# OTHER.net
KiCad netlist of a schematic drawn in Altium Designer
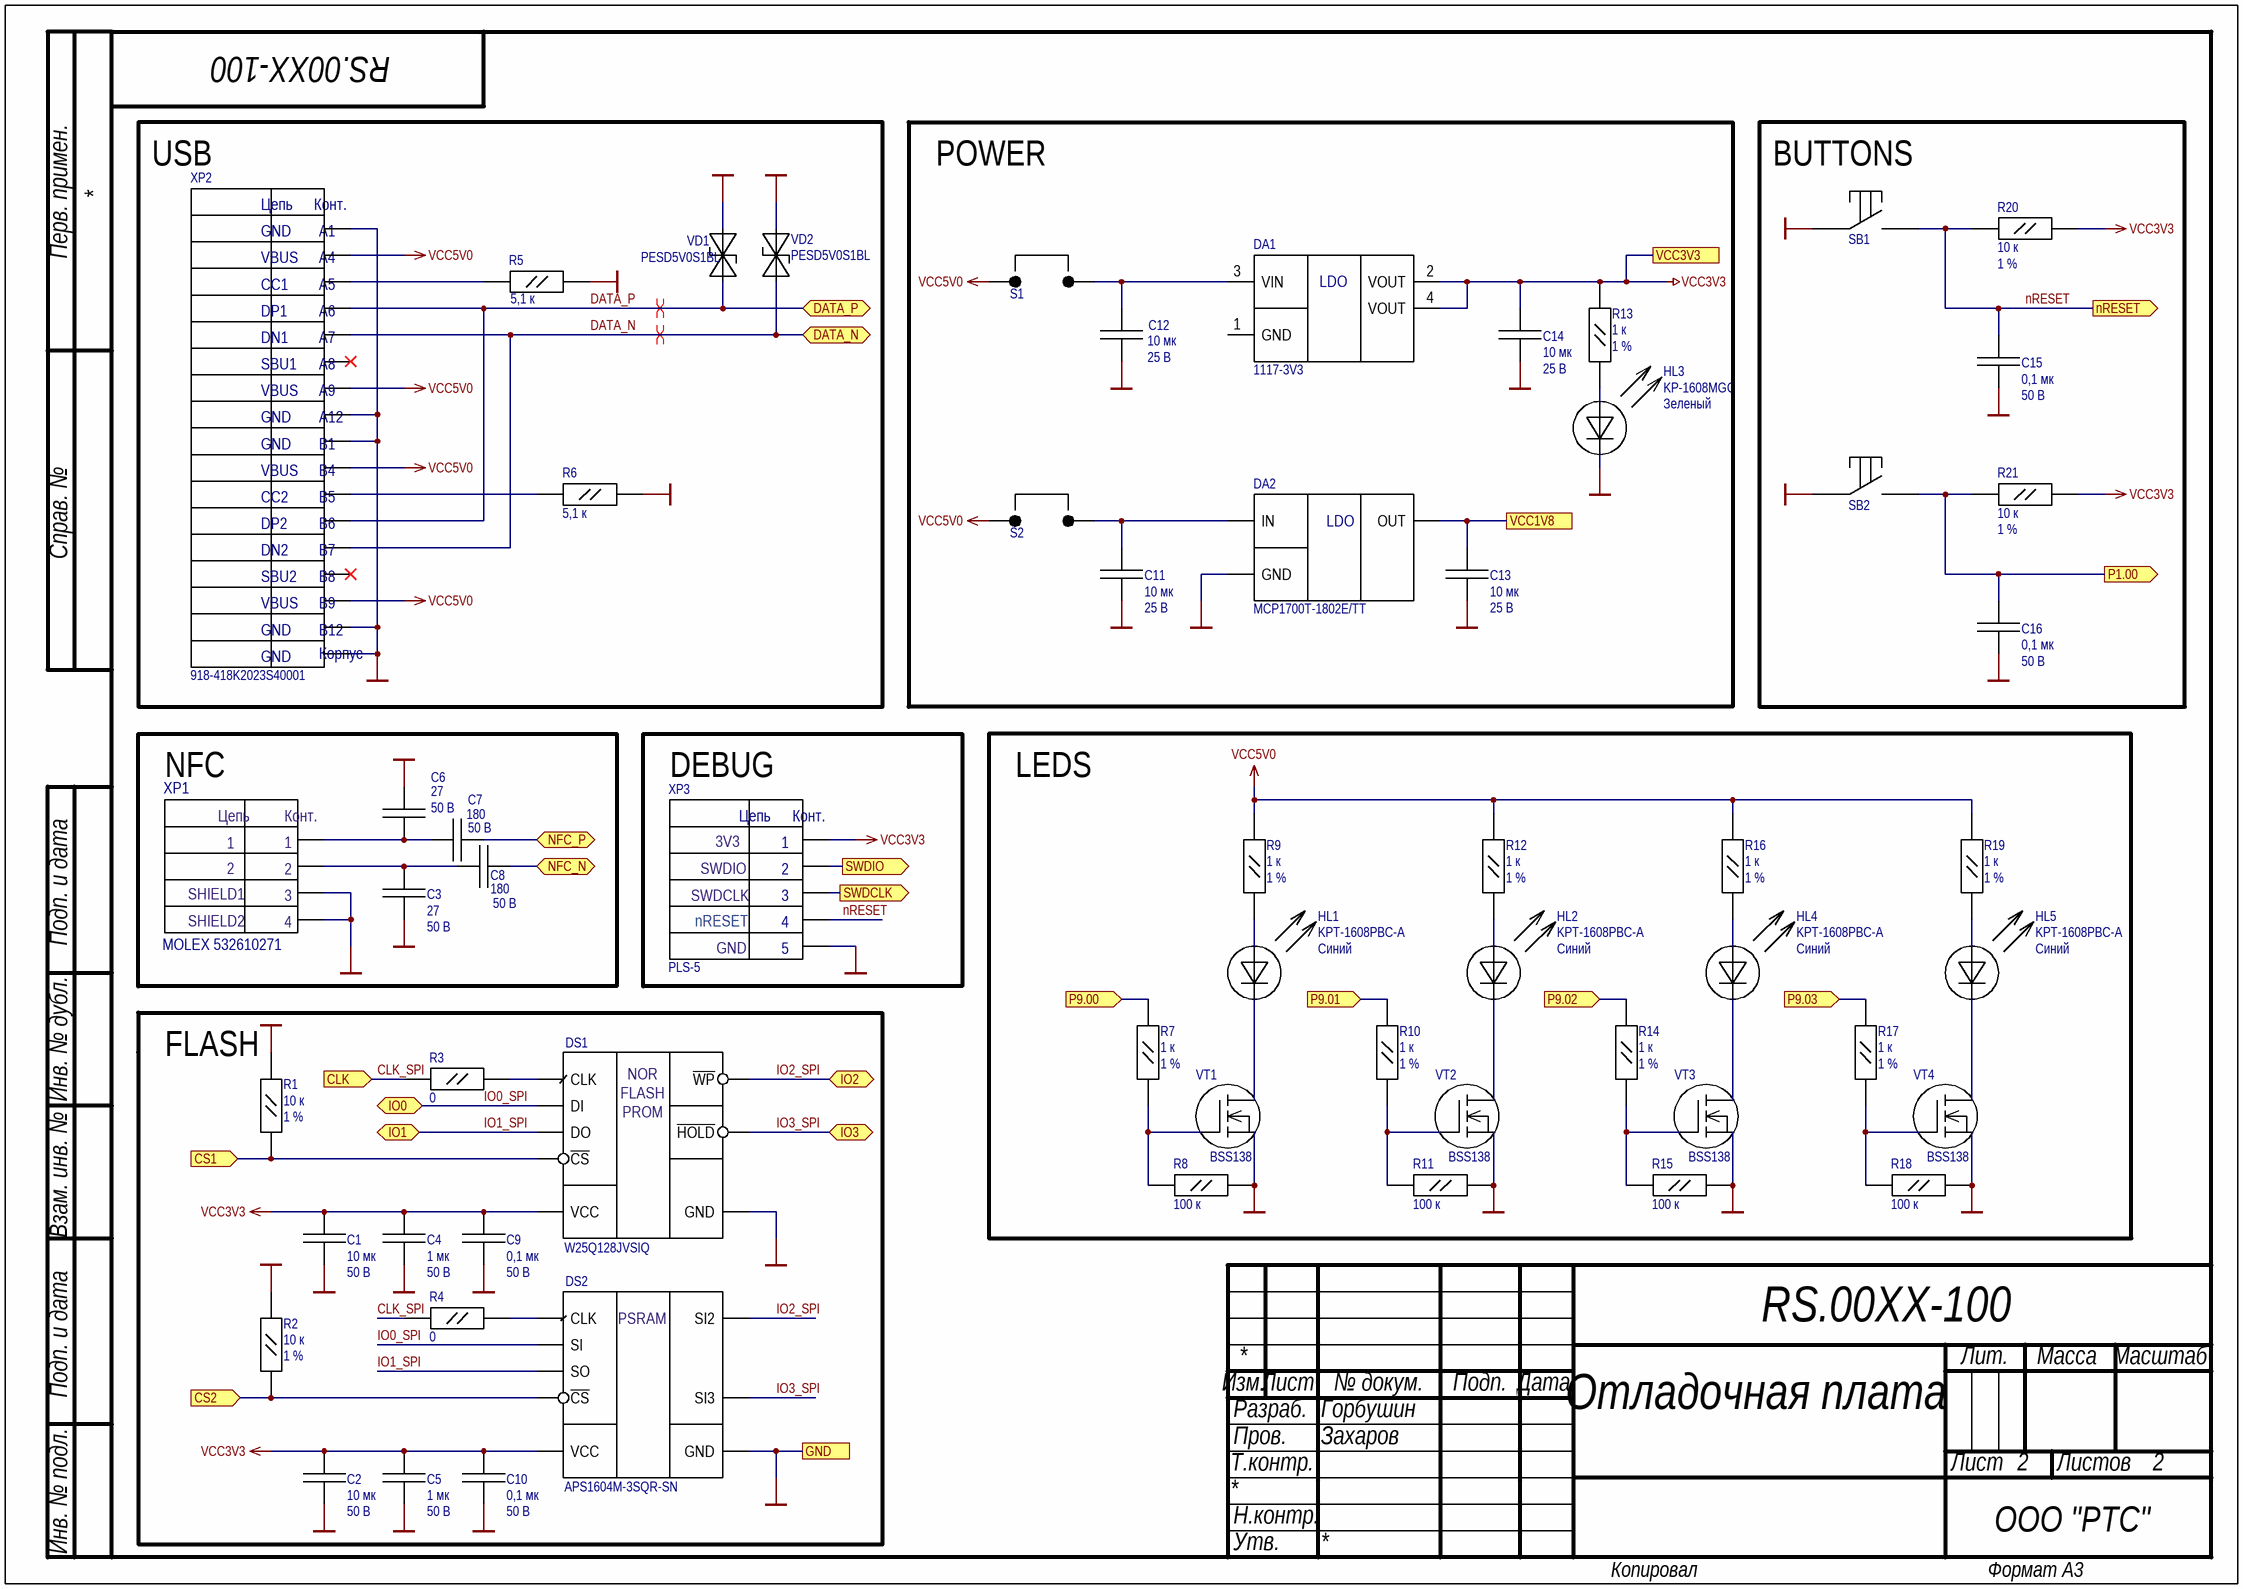
[diagram p0: OTHER.SchDoc]

(export (version "E")
  (design (tool "Eeschema 10.0.6"))
  (components
    (comp (ref "C1")
      (value "10 мк")
      (footprint "C_1210_Manual_mount")
      (description "Chip Monolithic Ceramic Capacitor")
      (fields
        (field (name "TOLERANCE") "20 %")
        (field (name "MANUFACTURER") "Murata Manufacturing")
        (field (name "RATED VOLTAGE") "50 В")
      )
      (libsource (lib "passive") (part "Capacitor"))
    )
    (comp (ref "C2")
      (value "10 мк")
      (footprint "C_1210_Manual_mount")
      (description "Chip Monolithic Ceramic Capacitor")
      (fields
        (field (name "TOLERANCE") "20 %")
        (field (name "MANUFACTURER") "Murata Manufacturing")
        (field (name "RATED VOLTAGE") "50 В")
      )
      (libsource (lib "passive") (part "Capacitor"))
    )
    (comp (ref "C3")
      (value "27")
      (footprint "C_0603_Manual_mount")
      (description "Chip Monolithic Ceramic Capacitor")
      (fields
        (field (name "TOLERANCE") "5 %")
        (field (name "MANUFACTURER") "Murata Manufacturing")
        (field (name "RATED VOLTAGE") "50 В")
      )
      (libsource (lib "passive") (part "Capacitor"))
    )
    (comp (ref "C4")
      (value "1 мк")
      (footprint "C_1206_Manual_mount")
      (description "Chip Monolithic Ceramic Capacitor")
      (fields
        (field (name "TOLERANCE") "10 %")
        (field (name "MANUFACTURER") "Murata Manufacturing")
        (field (name "RATED VOLTAGE") "50 В")
      )
      (libsource (lib "passive") (part "Capacitor"))
    )
    (comp (ref "C5")
      (value "1 мк")
      (footprint "C_1206_Manual_mount")
      (description "Chip Monolithic Ceramic Capacitor")
      (fields
        (field (name "TOLERANCE") "10 %")
        (field (name "MANUFACTURER") "Murata Manufacturing")
        (field (name "RATED VOLTAGE") "50 В")
      )
      (libsource (lib "passive") (part "Capacitor"))
    )
    (comp (ref "C6")
      (value "27")
      (footprint "C_0603_Manual_mount")
      (description "Chip Monolithic Ceramic Capacitor")
      (fields
        (field (name "TOLERANCE") "5 %")
        (field (name "MANUFACTURER") "Murata Manufacturing")
        (field (name "RATED VOLTAGE") "50 В")
      )
      (libsource (lib "passive") (part "Capacitor"))
    )
    (comp (ref "C7")
      (value "180")
      (footprint "C_0603_Manual_mount")
      (description "Chip Monolithic Ceramic Capacitor")
      (fields
        (field (name "TOLERANCE") "5 %")
        (field (name "MANUFACTURER") "Murata Manufacturing")
        (field (name "RATED VOLTAGE") "50 В")
      )
      (libsource (lib "passive") (part "Capacitor"))
    )
    (comp (ref "C8")
      (value "180")
      (footprint "C_0603_Manual_mount")
      (description "Chip Monolithic Ceramic Capacitor")
      (fields
        (field (name "TOLERANCE") "5 %")
        (field (name "MANUFACTURER") "Murata Manufacturing")
        (field (name "RATED VOLTAGE") "50 В")
      )
      (libsource (lib "passive") (part "Capacitor"))
    )
    (comp (ref "C9")
      (value "0,1 мк")
      (footprint "C_0603_Manual_mount")
      (description "Chip Monolithic Ceramic Capacitor")
      (fields
        (field (name "TOLERANCE") "10 %")
        (field (name "MANUFACTURER") "Murata Manufacturing")
        (field (name "RATED VOLTAGE") "50 В")
      )
      (libsource (lib "passive") (part "Capacitor"))
    )
    (comp (ref "C10")
      (value "0,1 мк")
      (footprint "C_0603_Manual_mount")
      (description "Chip Monolithic Ceramic Capacitor")
      (fields
        (field (name "TOLERANCE") "10 %")
        (field (name "MANUFACTURER") "Murata Manufacturing")
        (field (name "RATED VOLTAGE") "50 В")
      )
      (libsource (lib "passive") (part "Capacitor"))
    )
    (comp (ref "C11")
      (value "10 мк")
      (footprint "C_0603_Manual_mount")
      (description "Chip Monolithic Ceramic Capacitor")
      (fields
        (field (name "TOLERANCE") "20 %")
        (field (name "MANUFACTURER") "Murata Manufacturing")
        (field (name "RATED VOLTAGE") "25 В")
      )
      (libsource (lib "passive") (part "Capacitor"))
    )
    (comp (ref "C12")
      (value "10 мк")
      (footprint "C_0603_Manual_mount")
      (description "Chip Monolithic Ceramic Capacitor")
      (fields
        (field (name "TOLERANCE") "20 %")
        (field (name "MANUFACTURER") "Murata Manufacturing")
        (field (name "RATED VOLTAGE") "25 В")
      )
      (libsource (lib "passive") (part "Capacitor"))
    )
    (comp (ref "C13")
      (value "10 мк")
      (footprint "C_0603_Manual_mount")
      (description "Chip Monolithic Ceramic Capacitor")
      (fields
        (field (name "TOLERANCE") "20 %")
        (field (name "MANUFACTURER") "Murata Manufacturing")
        (field (name "RATED VOLTAGE") "25 В")
      )
      (libsource (lib "passive") (part "Capacitor"))
    )
    (comp (ref "C14")
      (value "10 мк")
      (footprint "C_0603_Manual_mount")
      (description "Chip Monolithic Ceramic Capacitor")
      (fields
        (field (name "TOLERANCE") "20 %")
        (field (name "MANUFACTURER") "Murata Manufacturing")
        (field (name "RATED VOLTAGE") "25 В")
      )
      (libsource (lib "passive") (part "Capacitor"))
    )
    (comp (ref "C15")
      (value "0,1 мк")
      (footprint "C_0603_Manual_mount")
      (description "Chip Monolithic Ceramic Capacitor")
      (fields
        (field (name "TOLERANCE") "10 %")
        (field (name "MANUFACTURER") "Murata Manufacturing")
        (field (name "RATED VOLTAGE") "50 В")
      )
      (libsource (lib "passive") (part "Capacitor"))
    )
    (comp (ref "C16")
      (value "0,1 мк")
      (footprint "C_0603_Manual_mount")
      (description "Chip Monolithic Ceramic Capacitor")
      (fields
        (field (name "TOLERANCE") "10 %")
        (field (name "MANUFACTURER") "Murata Manufacturing")
        (field (name "RATED VOLTAGE") "50 В")
      )
      (libsource (lib "passive") (part "Capacitor"))
    )
    (comp (ref "DA1")
      (value "1117-3V3")
      (footprint "SOT-223")
      (description "LOW DROP LINEAR VOLTAGE REGULATORS")
      (fields (field (name "MANUFACTURER") "Hottech"))
      (libsource (lib "dev_zakharkov") (part "1117-3V3"))
    )
    (comp (ref "DA2")
      (value "MCP1700T-1802E/TT")
      (footprint "SOT-23")
      (description "Low Quiescent Current LDO")
      (fields (field (name "MANUFACTURER") "Microchip Technology"))
      (libsource (lib "altium-lib") (part "MCP1700T-1802E/TT"))
    )
    (comp (ref "DS1")
      (value "W25Q128JVSIQ")
      (footprint "SOIC127P790X216-8N")
      (description "FLASH - NOR Memory IC 128Mb (16M x 8) SPI - Quad I/O, QPI, DTR 133 MHz 8-SOIC")
      (fields (field (name "MANUFACTURER") "Winbond"))
      (libsource (lib "Память24") (part "W25Q128JVSIQ"))
    )
    (comp (ref "DS2")
      (value "APS1604M-3SQR-SN")
      (footprint "APS1604M (SOP-8)")
      (fields (field (name "MANUFACTURER") "AP Memory"))
      (libsource (lib "Schlib1") (part "APS1604M-3SQR-SN"))
    )
    (comp (ref "HL1")
      (value "KPT-1608PBC-A")
      (footprint "LED_0603_Blue_Auto_mount")
      (description "SMD LED")
      (fields (field (name "MANUFACTURER") "Kingbright") (field (name "COLOR") "Синий"))
      (libsource (lib "altium-lib") (part "KPT-1608PBC-A"))
    )
    (comp (ref "HL2")
      (value "KPT-1608PBC-A")
      (footprint "LED_0603_Blue_Auto_mount")
      (description "SMD LED")
      (fields (field (name "MANUFACTURER") "Kingbright") (field (name "COLOR") "Синий"))
      (libsource (lib "altium-lib") (part "KPT-1608PBC-A"))
    )
    (comp (ref "HL3")
      (value "KP-1608MGC")
      (footprint "LED_0603_Green_Auto_mount")
      (description "SMD LED")
      (fields (field (name "MANUFACTURER") "Kingbright") (field (name "COLOR") "Зеленый"))
      (libsource (lib "altium-lib") (part "KP-1608MGC"))
    )
    (comp (ref "HL4")
      (value "KPT-1608PBC-A")
      (footprint "LED_0603_Blue_Auto_mount")
      (description "SMD LED")
      (fields (field (name "MANUFACTURER") "Kingbright") (field (name "COLOR") "Синий"))
      (libsource (lib "altium-lib") (part "KPT-1608PBC-A"))
    )
    (comp (ref "HL5")
      (value "KPT-1608PBC-A")
      (footprint "LED_0603_Blue_Auto_mount")
      (description "SMD LED")
      (fields (field (name "MANUFACTURER") "Kingbright") (field (name "COLOR") "Синий"))
      (libsource (lib "altium-lib") (part "KPT-1608PBC-A"))
    )
    (comp (ref "R1")
      (value "10 к")
      (footprint "R_0603_Manual_mount")
      (description "General Purpose Chip Resistor")
      (fields
        (field (name "MANUFACTURER") "YAGEO")
        (field (name "TOLERANCE") "1 %")
        (field (name "PART NUMBER") "RC0603FR-0710KL")
      )
      (libsource (lib "passive") (part "Resistor_0.125W_tol"))
    )
    (comp (ref "R2")
      (value "10 к")
      (footprint "R_0603_Manual_mount")
      (description "General Purpose Chip Resistor")
      (fields
        (field (name "MANUFACTURER") "YAGEO")
        (field (name "TOLERANCE") "1 %")
        (field (name "PART NUMBER") "RC0603FR-0710KL")
      )
      (libsource (lib "passive") (part "Resistor_0.125W_tol"))
    )
    (comp (ref "R3")
      (value "0")
      (footprint "R_0603_Manual_mount")
      (description "General Purpose Chip Resistor")
      (fields (field (name "TOLERANCE") "5 %") (field (name "MANUFACTURER") "YAGEO"))
      (libsource (lib "passive") (part "Resistor_0.125W"))
    )
    (comp (ref "R4")
      (value "0")
      (footprint "R_0603_Manual_mount")
      (description "General Purpose Chip Resistor")
      (fields (field (name "TOLERANCE") "5 %") (field (name "MANUFACTURER") "YAGEO"))
      (libsource (lib "passive") (part "Resistor_0.125W"))
    )
    (comp (ref "R5")
      (value "5,1 к")
      (footprint "R_0603_Manual_mount")
      (description "General Purpose Chip Resistor")
      (fields (field (name "TOLERANCE") "5 %") (field (name "MANUFACTURER") "YAGEO"))
      (libsource (lib "passive") (part "Resistor_0.125W"))
    )
    (comp (ref "R6")
      (value "5,1 к")
      (footprint "R_0603_Manual_mount")
      (description "General Purpose Chip Resistor")
      (fields (field (name "TOLERANCE") "5 %") (field (name "MANUFACTURER") "YAGEO"))
      (libsource (lib "passive") (part "Resistor_0.125W"))
    )
    (comp (ref "R7")
      (value "1 к")
      (footprint "R_0603_Manual_mount")
      (description "General Purpose Chip Resistor")
      (fields
        (field (name "MANUFACTURER") "YAGEO")
        (field (name "TOLERANCE") "1 %")
        (field (name "PART NUMBER") "RC0603FR-071KL")
      )
      (libsource (lib "passive") (part "Resistor_0.125W_tol"))
    )
    (comp (ref "R8")
      (value "100 к")
      (footprint "R_0603_Manual_mount")
      (description "General Purpose Chip Resistor")
      (fields (field (name "TOLERANCE") "5 %") (field (name "MANUFACTURER") "YAGEO"))
      (libsource (lib "passive") (part "Resistor_0.125W"))
    )
    (comp (ref "R9")
      (value "1 к")
      (footprint "R_0603_Manual_mount")
      (description "General Purpose Chip Resistor")
      (fields
        (field (name "MANUFACTURER") "YAGEO")
        (field (name "TOLERANCE") "1 %")
        (field (name "PART NUMBER") "RC0603FR-071KL")
      )
      (libsource (lib "passive") (part "Resistor_0.125W_tol"))
    )
    (comp (ref "R10")
      (value "1 к")
      (footprint "R_0603_Manual_mount")
      (description "General Purpose Chip Resistor")
      (fields
        (field (name "MANUFACTURER") "YAGEO")
        (field (name "TOLERANCE") "1 %")
        (field (name "PART NUMBER") "RC0603FR-071KL")
      )
      (libsource (lib "passive") (part "Resistor_0.125W_tol"))
    )
    (comp (ref "R11")
      (value "100 к")
      (footprint "R_0603_Manual_mount")
      (description "General Purpose Chip Resistor")
      (fields (field (name "TOLERANCE") "5 %") (field (name "MANUFACTURER") "YAGEO"))
      (libsource (lib "passive") (part "Resistor_0.125W"))
    )
    (comp (ref "R12")
      (value "1 к")
      (footprint "R_0603_Manual_mount")
      (description "General Purpose Chip Resistor")
      (fields
        (field (name "MANUFACTURER") "YAGEO")
        (field (name "TOLERANCE") "1 %")
        (field (name "PART NUMBER") "RC0603FR-071KL")
      )
      (libsource (lib "passive") (part "Resistor_0.125W_tol"))
    )
    (comp (ref "R13")
      (value "1 к")
      (footprint "R_0603_Manual_mount")
      (description "General Purpose Chip Resistor")
      (fields
        (field (name "MANUFACTURER") "YAGEO")
        (field (name "TOLERANCE") "1 %")
        (field (name "PART NUMBER") "RC0603FR-071KL")
      )
      (libsource (lib "passive") (part "Resistor_0.125W_tol"))
    )
    (comp (ref "R14")
      (value "1 к")
      (footprint "R_0603_Manual_mount")
      (description "General Purpose Chip Resistor")
      (fields
        (field (name "MANUFACTURER") "YAGEO")
        (field (name "TOLERANCE") "1 %")
        (field (name "PART NUMBER") "RC0603FR-071KL")
      )
      (libsource (lib "passive") (part "Resistor_0.125W_tol"))
    )
    (comp (ref "R15")
      (value "100 к")
      (footprint "R_0603_Manual_mount")
      (description "General Purpose Chip Resistor")
      (fields (field (name "TOLERANCE") "5 %") (field (name "MANUFACTURER") "YAGEO"))
      (libsource (lib "passive") (part "Resistor_0.125W"))
    )
    (comp (ref "R16")
      (value "1 к")
      (footprint "R_0603_Manual_mount")
      (description "General Purpose Chip Resistor")
      (fields
        (field (name "MANUFACTURER") "YAGEO")
        (field (name "TOLERANCE") "1 %")
        (field (name "PART NUMBER") "RC0603FR-071KL")
      )
      (libsource (lib "passive") (part "Resistor_0.125W_tol"))
    )
    (comp (ref "R17")
      (value "1 к")
      (footprint "R_0603_Manual_mount")
      (description "General Purpose Chip Resistor")
      (fields
        (field (name "MANUFACTURER") "YAGEO")
        (field (name "TOLERANCE") "1 %")
        (field (name "PART NUMBER") "RC0603FR-071KL")
      )
      (libsource (lib "passive") (part "Resistor_0.125W_tol"))
    )
    (comp (ref "R18")
      (value "100 к")
      (footprint "R_0603_Manual_mount")
      (description "General Purpose Chip Resistor")
      (fields (field (name "TOLERANCE") "5 %") (field (name "MANUFACTURER") "YAGEO"))
      (libsource (lib "passive") (part "Resistor_0.125W"))
    )
    (comp (ref "R19")
      (value "1 к")
      (footprint "R_0603_Manual_mount")
      (description "General Purpose Chip Resistor")
      (fields
        (field (name "MANUFACTURER") "YAGEO")
        (field (name "TOLERANCE") "1 %")
        (field (name "PART NUMBER") "RC0603FR-071KL")
      )
      (libsource (lib "passive") (part "Resistor_0.125W_tol"))
    )
    (comp (ref "R20")
      (value "10 к")
      (footprint "R_0603_Manual_mount")
      (description "General Purpose Chip Resistor")
      (fields
        (field (name "MANUFACTURER") "YAGEO")
        (field (name "TOLERANCE") "1 %")
        (field (name "PART NUMBER") "RC0603FR-0710KL")
      )
      (libsource (lib "passive") (part "Resistor_0.125W_tol"))
    )
    (comp (ref "R21")
      (value "10 к")
      (footprint "R_0603_Manual_mount")
      (description "General Purpose Chip Resistor")
      (fields
        (field (name "MANUFACTURER") "YAGEO")
        (field (name "TOLERANCE") "1 %")
        (field (name "PART NUMBER") "RC0603FR-0710KL")
      )
      (libsource (lib "passive") (part "Resistor_0.125W_tol"))
    )
    (comp (ref "S1")
      (value "0")
      (footprint "Wedge Jumper 0603")
      (description "Wedge jumper")
      (libsource (lib "altium-lib") (part "Wedge jumper"))
    )
    (comp (ref "S2")
      (value "0")
      (footprint "Wedge Jumper 0603")
      (description "Wedge jumper")
      (libsource (lib "altium-lib") (part "Wedge jumper"))
    )
    (comp (ref "SB1")
      (value "Tact_switch")
      (footprint "Tact_switch_6x6x4.3")
      (description "SMD pushbutton")
      (fields (field (name "MANUFACTURER") "NONAME"))
      (libsource (lib "altium-lib") (part "Tact_switch"))
    )
    (comp (ref "SB2")
      (value "Tact_switch")
      (footprint "Tact_switch_6x6x4.3")
      (description "SMD pushbutton")
      (fields (field (name "MANUFACTURER") "NONAME"))
      (libsource (lib "altium-lib") (part "Tact_switch"))
    )
    (comp (ref "VD1")
      (value "PESD5V0S1BL")
      (footprint "SOD-882")
      (description "Low capacitance bidirectional ESD protection diodes")
      (fields (field (name "MANUFACTURER") "NXP"))
      (libsource (lib "dev_zakharkov") (part "PESD5V0S1BL"))
    )
    (comp (ref "VD2")
      (value "PESD5V0S1BL")
      (footprint "SOD-882")
      (description "Low capacitance bidirectional ESD protection diodes")
      (fields (field (name "MANUFACTURER") "NXP"))
      (libsource (lib "dev_zakharkov") (part "PESD5V0S1BL"))
    )
    (comp (ref "VT1")
      (value "BSS138")
      (footprint "SOT-23")
      (description "N-Channel Logic Level Enhancement Mode Field Effect Transistor")
      (fields (field (name "MANUFACTURER") "Fairchild Semiconductor"))
      (libsource (lib "altium-lib") (part "BSS138"))
    )
    (comp (ref "VT2")
      (value "BSS138")
      (footprint "SOT-23")
      (description "N-Channel Logic Level Enhancement Mode Field Effect Transistor")
      (fields (field (name "MANUFACTURER") "Fairchild Semiconductor"))
      (libsource (lib "altium-lib") (part "BSS138"))
    )
    (comp (ref "VT3")
      (value "BSS138")
      (footprint "SOT-23")
      (description "N-Channel Logic Level Enhancement Mode Field Effect Transistor")
      (fields (field (name "MANUFACTURER") "Fairchild Semiconductor"))
      (libsource (lib "altium-lib") (part "BSS138"))
    )
    (comp (ref "VT4")
      (value "BSS138")
      (footprint "SOT-23")
      (description "N-Channel Logic Level Enhancement Mode Field Effect Transistor")
      (fields (field (name "MANUFACTURER") "Fairchild Semiconductor"))
      (libsource (lib "altium-lib") (part "BSS138"))
    )
    (comp (ref "XP1")
      (value "MOLEX 532610271")
      (footprint "MOLEX_532610271")
      (description "Connector Header Surface Mount, Right Angle 2 position 0.049 (1.25mm)")
      (fields (field (name "MANUFACTURER") "MOLEX"))
      (libsource (lib "антенна24") (part "532610271"))
    )
    (comp (ref "XP2")
      (value "918-418K2023S40001")
      (footprint "918-418K2023S40001")
      (description "Female Type-C SMD USB Connectors")
      (fields (field (name "MANUFACTURER") "JING"))
      (libsource (lib "dev_zakharkov") (part "918-418K2023S40001"))
    )
    (comp (ref "XP3")
      (value "PLS-5")
      (footprint "PLS-5")
      (description "PLS connector")
      (fields (field (name "MANUFACTURER") "NONAME"))
      (libsource (lib "altium-lib") (part "PLS-5"))
    )
  )
  (nets
    (net (code "1") (name "/CLK_SPI") (class "Default")
      (node (ref "R3") (pin "1") (pinfunction "1_1") (pintype "passive"))
      (node (ref "R4") (pin "1") (pinfunction "1_1") (pintype "passive"))
    )
    (net (code "2") (name "/CS1") (class "Default")
      (node (ref "DS1") (pin "1") (pinfunction "~{CS}_1") (pintype "passive"))
      (node (ref "R1") (pin "1") (pinfunction "1_1") (pintype "passive"))
    )
    (net (code "3") (name "/CS2") (class "Default")
      (node (ref "DS2") (pin "1") (pinfunction "~{CS}_1") (pintype "passive"))
      (node (ref "R2") (pin "1") (pinfunction "1_1") (pintype "passive"))
    )
    (net (code "4") (name "/DATA_N") (class "Default")
      (node (ref "VD2") (pin "2") (pinfunction "2_2") (pintype "passive"))
      (node (ref "XP2") (pin "A7") (pinfunction "A7_A7") (pintype "passive"))
      (node (ref "XP2") (pin "B7") (pinfunction "B7_B7") (pintype "passive"))
    )
    (net (code "5") (name "/DATA_P") (class "Default")
      (node (ref "VD1") (pin "2") (pinfunction "2_2") (pintype "passive"))
      (node (ref "XP2") (pin "A6") (pinfunction "A6_A6") (pintype "passive"))
      (node (ref "XP2") (pin "B6") (pinfunction "B6_B6") (pintype "passive"))
    )
    (net (code "6") (name "/IO0_SPI") (class "Default")
      (node (ref "DS1") (pin "5") (pinfunction "DI_5") (pintype "passive"))
      (node (ref "DS2") (pin "5") (pinfunction "SI_5") (pintype "passive"))
    )
    (net (code "7") (name "/IO1_SPI") (class "Default")
      (node (ref "DS1") (pin "2") (pinfunction "DO_2") (pintype "passive"))
      (node (ref "DS2") (pin "2") (pinfunction "SO_2") (pintype "passive"))
    )
    (net (code "8") (name "/IO2_SPI") (class "Default")
      (node (ref "DS1") (pin "3") (pinfunction "~{WP}_3") (pintype "passive"))
      (node (ref "DS2") (pin "3") (pinfunction "SI2_3") (pintype "passive"))
    )
    (net (code "9") (name "/IO3_SPI") (class "Default")
      (node (ref "DS1") (pin "7") (pinfunction "~{HOLD}_7") (pintype "passive"))
      (node (ref "DS2") (pin "7") (pinfunction "SI3_7") (pintype "passive"))
    )
    (net (code "10") (name "/NFC_N") (class "Default")
      (node (ref "C8") (pin "1") (pinfunction "1_1") (pintype "passive"))
    )
    (net (code "11") (name "/NFC_P") (class "Default")
      (node (ref "C7") (pin "1") (pinfunction "1_1") (pintype "passive"))
    )
    (net (code "12") (name "/P1.00") (class "Default")
      (node (ref "C16") (pin "1") (pinfunction "1_1") (pintype "passive"))
      (node (ref "R21") (pin "1") (pinfunction "1_1") (pintype "passive"))
      (node (ref "SB2") (pin "2") (pinfunction "2_2") (pintype "passive"))
    )
    (net (code "13") (name "/P9.00") (class "Default")
      (node (ref "R7") (pin "1") (pinfunction "1_1") (pintype "passive"))
    )
    (net (code "14") (name "/P9.01") (class "Default")
      (node (ref "R10") (pin "1") (pinfunction "1_1") (pintype "passive"))
    )
    (net (code "15") (name "/P9.02") (class "Default")
      (node (ref "R14") (pin "1") (pinfunction "1_1") (pintype "passive"))
    )
    (net (code "16") (name "/P9.03") (class "Default")
      (node (ref "R17") (pin "1") (pinfunction "1_1") (pintype "passive"))
    )
    (net (code "17") (name "/SWDCLK") (class "Default")
      (node (ref "XP3") (pin "3") (pinfunction "3_3") (pintype "passive"))
    )
    (net (code "18") (name "/SWDIO") (class "Default")
      (node (ref "XP3") (pin "2") (pinfunction "2_2") (pintype "passive"))
    )
    (net (code "19") (name "/VCC1V8") (class "Default")
      (node (ref "C13") (pin "1") (pinfunction "1_1") (pintype "passive"))
      (node (ref "DA2") (pin "2") (pinfunction "OUT_2") (pintype "passive"))
    )
    (net (code "20") (name "/nRESET") (class "Default")
      (node (ref "C15") (pin "1") (pinfunction "1_1") (pintype "passive"))
      (node (ref "R20") (pin "1") (pinfunction "1_1") (pintype "passive"))
      (node (ref "SB1") (pin "2") (pinfunction "2_2") (pintype "passive"))
      (node (ref "XP3") (pin "4") (pinfunction "4_4") (pintype "passive"))
    )
    (net (code "21") (name "GND") (class "Default")
      (node (ref "C1") (pin "2") (pinfunction "2_2") (pintype "passive"))
      (node (ref "C10") (pin "2") (pinfunction "2_2") (pintype "passive"))
      (node (ref "C11") (pin "2") (pinfunction "2_2") (pintype "passive"))
      (node (ref "C12") (pin "2") (pinfunction "2_2") (pintype "passive"))
      (node (ref "C13") (pin "2") (pinfunction "2_2") (pintype "passive"))
      (node (ref "C14") (pin "2") (pinfunction "2_2") (pintype "passive"))
      (node (ref "C15") (pin "2") (pinfunction "2_2") (pintype "passive"))
      (node (ref "C16") (pin "2") (pinfunction "2_2") (pintype "passive"))
      (node (ref "C2") (pin "2") (pinfunction "2_2") (pintype "passive"))
      (node (ref "C3") (pin "2") (pinfunction "2_2") (pintype "passive"))
      (node (ref "C4") (pin "2") (pinfunction "2_2") (pintype "passive"))
      (node (ref "C5") (pin "2") (pinfunction "2_2") (pintype "passive"))
      (node (ref "C6") (pin "1") (pinfunction "1_1") (pintype "passive"))
      (node (ref "C9") (pin "2") (pinfunction "2_2") (pintype "passive"))
      (node (ref "DA2") (pin "1") (pinfunction "GND_1") (pintype "passive"))
      (node (ref "DS1") (pin "4") (pinfunction "GND_4") (pintype "power_in"))
      (node (ref "DS2") (pin "4") (pinfunction "GND_4") (pintype "passive"))
      (node (ref "HL3") (pin "C") (pinfunction "C_C") (pintype "passive"))
      (node (ref "R1") (pin "2") (pinfunction "2_2") (pintype "passive"))
      (node (ref "R11") (pin "2") (pinfunction "2_2") (pintype "passive"))
      (node (ref "R15") (pin "2") (pinfunction "2_2") (pintype "passive"))
      (node (ref "R18") (pin "2") (pinfunction "2_2") (pintype "passive"))
      (node (ref "R2") (pin "2") (pinfunction "2_2") (pintype "passive"))
      (node (ref "R5") (pin "2") (pinfunction "2_2") (pintype "passive"))
      (node (ref "R6") (pin "2") (pinfunction "2_2") (pintype "passive"))
      (node (ref "R8") (pin "2") (pinfunction "2_2") (pintype "passive"))
      (node (ref "SB1") (pin "1") (pinfunction "1_1") (pintype "passive"))
      (node (ref "SB2") (pin "1") (pinfunction "1_1") (pintype "passive"))
      (node (ref "VD1") (pin "1") (pinfunction "1_1") (pintype "passive"))
      (node (ref "VD2") (pin "1") (pinfunction "1_1") (pintype "passive"))
      (node (ref "VT1") (pin "2") (pinfunction "S_2") (pintype "passive"))
      (node (ref "VT2") (pin "2") (pinfunction "S_2") (pintype "passive"))
      (node (ref "VT3") (pin "2") (pinfunction "S_2") (pintype "passive"))
      (node (ref "VT4") (pin "2") (pinfunction "S_2") (pintype "passive"))
      (node (ref "XP1") (pin "S1") (pinfunction "SHIELD1_S1") (pintype "passive"))
      (node (ref "XP1") (pin "S2") (pinfunction "SHIELD2_S2") (pintype "passive"))
      (node (ref "XP2") (pin "0") (pinfunction "0_0") (pintype "passive"))
      (node (ref "XP2") (pin "A1") (pinfunction "A1_A1") (pintype "passive"))
      (node (ref "XP2") (pin "A12") (pinfunction "A12_A12") (pintype "passive"))
      (node (ref "XP2") (pin "B1") (pinfunction "7_B1") (pintype "passive"))
      (node (ref "XP2") (pin "B12") (pinfunction "B12_B12") (pintype "passive"))
      (node (ref "XP3") (pin "5") (pinfunction "5_5") (pintype "passive"))
    )
    (net (code "22") (name "Net-(C3-Pad1)") (class "Default")
      (node (ref "C3") (pin "1") (pinfunction "1_1") (pintype "passive"))
      (node (ref "C8") (pin "2") (pinfunction "2_2") (pintype "passive"))
      (node (ref "XP1") (pin "2") (pinfunction "2_2") (pintype "passive"))
    )
    (net (code "23") (name "Net-(C6-Pad2)") (class "Default")
      (node (ref "C6") (pin "2") (pinfunction "2_2") (pintype "passive"))
      (node (ref "C7") (pin "2") (pinfunction "2_2") (pintype "passive"))
      (node (ref "XP1") (pin "1") (pinfunction "1_1") (pintype "passive"))
    )
    (net (code "24") (name "Net-(DA1-VIN)") (class "Default")
      (node (ref "C12") (pin "1") (pinfunction "1_1") (pintype "passive"))
      (node (ref "DA1") (pin "3") (pinfunction "VIN_3") (pintype "passive"))
      (node (ref "S1") (pin "2") (pinfunction "2_2") (pintype "passive"))
    )
    (net (code "25") (name "Net-(DA2-IN)") (class "Default")
      (node (ref "C11") (pin "1") (pinfunction "1_1") (pintype "passive"))
      (node (ref "DA2") (pin "3") (pinfunction "IN_3") (pintype "passive"))
      (node (ref "S2") (pin "2") (pinfunction "2_2") (pintype "passive"))
    )
    (net (code "26") (name "Net-(DS1-CLK)") (class "Default")
      (node (ref "DS1") (pin "6") (pinfunction "CLK_6") (pintype "passive"))
      (node (ref "R3") (pin "2") (pinfunction "2_2") (pintype "passive"))
    )
    (net (code "27") (name "Net-(DS2-CLK)") (class "Default")
      (node (ref "DS2") (pin "6") (pinfunction "CLK_6") (pintype "passive"))
      (node (ref "R4") (pin "2") (pinfunction "2_2") (pintype "passive"))
    )
    (net (code "28") (name "Net-(HL1-PadA)") (class "Default")
      (node (ref "HL1") (pin "A") (pinfunction "A_A") (pintype "passive"))
      (node (ref "R9") (pin "2") (pinfunction "2_2") (pintype "passive"))
    )
    (net (code "29") (name "Net-(HL2-PadA)") (class "Default")
      (node (ref "HL2") (pin "A") (pinfunction "A_A") (pintype "passive"))
      (node (ref "R12") (pin "2") (pinfunction "2_2") (pintype "passive"))
    )
    (net (code "30") (name "Net-(HL3-PadA)") (class "Default")
      (node (ref "HL3") (pin "A") (pinfunction "A_A") (pintype "passive"))
      (node (ref "R13") (pin "2") (pinfunction "2_2") (pintype "passive"))
    )
    (net (code "31") (name "Net-(HL4-PadA)") (class "Default")
      (node (ref "HL4") (pin "A") (pinfunction "A_A") (pintype "passive"))
      (node (ref "R16") (pin "2") (pinfunction "2_2") (pintype "passive"))
    )
    (net (code "32") (name "Net-(HL5-PadA)") (class "Default")
      (node (ref "HL5") (pin "A") (pinfunction "A_A") (pintype "passive"))
      (node (ref "R19") (pin "2") (pinfunction "2_2") (pintype "passive"))
    )
    (net (code "33") (name "Net-(R5-Pad1)") (class "Default")
      (node (ref "R5") (pin "1") (pinfunction "1_1") (pintype "passive"))
      (node (ref "XP2") (pin "A5") (pinfunction "A5_A5") (pintype "passive"))
    )
    (net (code "34") (name "Net-(R6-Pad1)") (class "Default")
      (node (ref "R6") (pin "1") (pinfunction "1_1") (pintype "passive"))
      (node (ref "XP2") (pin "B5") (pinfunction "B5_B5") (pintype "passive"))
    )
    (net (code "35") (name "Net-(VT1-D)") (class "Default")
      (node (ref "HL1") (pin "C") (pinfunction "C_C") (pintype "passive"))
      (node (ref "VT1") (pin "3") (pinfunction "D_3") (pintype "passive"))
    )
    (net (code "36") (name "Net-(VT1-G)") (class "Default")
      (node (ref "R7") (pin "2") (pinfunction "2_2") (pintype "passive"))
      (node (ref "R8") (pin "1") (pinfunction "1_1") (pintype "passive"))
      (node (ref "VT1") (pin "1") (pinfunction "G_1") (pintype "passive"))
    )
    (net (code "37") (name "Net-(VT2-D)") (class "Default")
      (node (ref "HL2") (pin "C") (pinfunction "C_C") (pintype "passive"))
      (node (ref "VT2") (pin "3") (pinfunction "D_3") (pintype "passive"))
    )
    (net (code "38") (name "Net-(VT2-G)") (class "Default")
      (node (ref "R10") (pin "2") (pinfunction "2_2") (pintype "passive"))
      (node (ref "R11") (pin "1") (pinfunction "1_1") (pintype "passive"))
      (node (ref "VT2") (pin "1") (pinfunction "G_1") (pintype "passive"))
    )
    (net (code "39") (name "Net-(VT3-D)") (class "Default")
      (node (ref "HL4") (pin "C") (pinfunction "C_C") (pintype "passive"))
      (node (ref "VT3") (pin "3") (pinfunction "D_3") (pintype "passive"))
    )
    (net (code "40") (name "Net-(VT3-G)") (class "Default")
      (node (ref "R14") (pin "2") (pinfunction "2_2") (pintype "passive"))
      (node (ref "R15") (pin "1") (pinfunction "1_1") (pintype "passive"))
      (node (ref "VT3") (pin "1") (pinfunction "G_1") (pintype "passive"))
    )
    (net (code "41") (name "Net-(VT4-D)") (class "Default")
      (node (ref "HL5") (pin "C") (pinfunction "C_C") (pintype "passive"))
      (node (ref "VT4") (pin "3") (pinfunction "D_3") (pintype "passive"))
    )
    (net (code "42") (name "Net-(VT4-G)") (class "Default")
      (node (ref "R17") (pin "2") (pinfunction "2_2") (pintype "passive"))
      (node (ref "R18") (pin "1") (pinfunction "1_1") (pintype "passive"))
      (node (ref "VT4") (pin "1") (pinfunction "G_1") (pintype "passive"))
    )
    (net (code "43") (name "VCC3V3") (class "Default")
      (node (ref "C1") (pin "1") (pinfunction "1_1") (pintype "passive"))
      (node (ref "C10") (pin "1") (pinfunction "1_1") (pintype "passive"))
      (node (ref "C14") (pin "1") (pinfunction "1_1") (pintype "passive"))
      (node (ref "C2") (pin "1") (pinfunction "1_1") (pintype "passive"))
      (node (ref "C4") (pin "1") (pinfunction "1_1") (pintype "passive"))
      (node (ref "C5") (pin "1") (pinfunction "1_1") (pintype "passive"))
      (node (ref "C9") (pin "1") (pinfunction "1_1") (pintype "passive"))
      (node (ref "DA1") (pin "2") (pinfunction "VOUT_2") (pintype "passive"))
      (node (ref "DA1") (pin "4") (pinfunction "VOUT_4") (pintype "passive"))
      (node (ref "DS1") (pin "8") (pinfunction "VCC_8") (pintype "power_in"))
      (node (ref "DS2") (pin "8") (pinfunction "VCC_8") (pintype "passive"))
      (node (ref "R13") (pin "1") (pinfunction "1_1") (pintype "passive"))
      (node (ref "R20") (pin "2") (pinfunction "2_2") (pintype "passive"))
      (node (ref "R21") (pin "2") (pinfunction "2_2") (pintype "passive"))
      (node (ref "XP3") (pin "1") (pinfunction "1_1") (pintype "passive"))
    )
    (net (code "44") (name "VCC5V0") (class "Default")
      (node (ref "R12") (pin "1") (pinfunction "1_1") (pintype "passive"))
      (node (ref "R16") (pin "1") (pinfunction "1_1") (pintype "passive"))
      (node (ref "R19") (pin "1") (pinfunction "1_1") (pintype "passive"))
      (node (ref "R9") (pin "1") (pinfunction "1_1") (pintype "passive"))
      (node (ref "S1") (pin "1") (pinfunction "1_1") (pintype "passive"))
      (node (ref "S2") (pin "1") (pinfunction "1_1") (pintype "passive"))
      (node (ref "XP2") (pin "A4") (pinfunction "A4_A4") (pintype "passive"))
      (node (ref "XP2") (pin "A9") (pinfunction "A9_A9") (pintype "passive"))
      (node (ref "XP2") (pin "B4") (pinfunction "B4_B4") (pintype "passive"))
      (node (ref "XP2") (pin "B9") (pinfunction "B9_B9") (pintype "passive"))
    )
    (net (code "45") (name "unconnected-(DA1-GND-Pad1)") (class "Default")
      (node (ref "DA1") (pin "1") (pinfunction "GND_1") (pintype "passive"))
    )
    (net (code "46") (name "unconnected-(XP2-PadA8)") (class "Default")
      (node (ref "XP2") (pin "A8") (pinfunction "A8_A8") (pintype "passive+no_connect"))
    )
    (net (code "47") (name "unconnected-(XP2-PadB8)") (class "Default")
      (node (ref "XP2") (pin "B8") (pinfunction "B8_B8") (pintype "passive+no_connect"))
    )
  )
)
